# RELAYULN.net
KiCad netlist of a schematic drawn in EAGLE
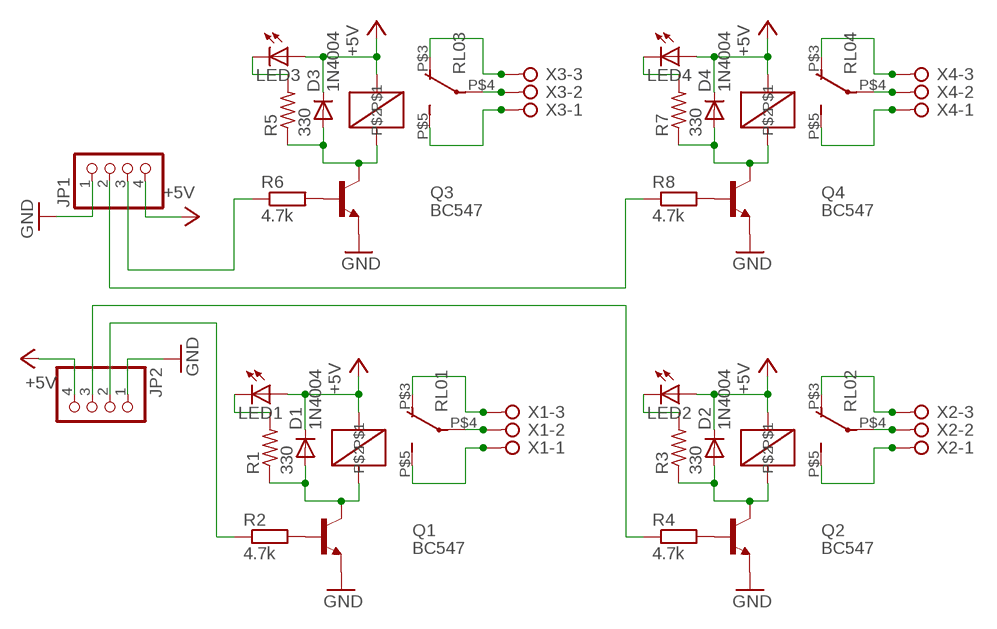
[diagram p0: schematic, sheet 1]

(export (version "E")
  (design (tool "Eeschema 10.0.6"))
  (components
    (comp (ref "D1")
      (value "1N4004")
      (footprint "eagle-import:DO41-10")
      (libsource (lib "eagle-import") (part "1N4004"))
    )
    (comp (ref "D2")
      (value "1N4004")
      (footprint "eagle-import:DO41-10")
      (libsource (lib "eagle-import") (part "1N4004"))
    )
    (comp (ref "D3")
      (value "1N4004")
      (footprint "eagle-import:DO41-10")
      (libsource (lib "eagle-import") (part "1N4004"))
    )
    (comp (ref "D4")
      (value "1N4004")
      (footprint "eagle-import:DO41-10")
      (libsource (lib "eagle-import") (part "1N4004"))
    )
    (comp (ref "JP1")
      (value "PINHD-1X4")
      (footprint "eagle-import:1X04")
      (libsource (lib "eagle-import") (part "PINHD-1X4"))
    )
    (comp (ref "JP2")
      (value "PINHD-1X4")
      (footprint "eagle-import:1X04")
      (libsource (lib "eagle-import") (part "PINHD-1X4"))
    )
    (comp (ref "LED1")
      (value "LED3MM")
      (footprint "eagle-import:LED3MM")
      (libsource (lib "eagle-import") (part "LED3MM"))
    )
    (comp (ref "LED2")
      (value "LED3MM")
      (footprint "eagle-import:LED3MM")
      (libsource (lib "eagle-import") (part "LED3MM"))
    )
    (comp (ref "LED3")
      (value "LED3MM")
      (footprint "eagle-import:LED3MM")
      (libsource (lib "eagle-import") (part "LED3MM"))
    )
    (comp (ref "LED4")
      (value "LED3MM")
      (footprint "eagle-import:LED3MM")
      (libsource (lib "eagle-import") (part "LED3MM"))
    )
    (comp (ref "Q1")
      (value "BC547")
      (footprint "eagle-import:TO92")
      (libsource (lib "eagle-import") (part "BC547"))
    )
    (comp (ref "Q2")
      (value "BC547")
      (footprint "eagle-import:TO92")
      (libsource (lib "eagle-import") (part "BC547"))
    )
    (comp (ref "Q3")
      (value "BC547")
      (footprint "eagle-import:TO92")
      (libsource (lib "eagle-import") (part "BC547"))
    )
    (comp (ref "Q4")
      (value "BC547")
      (footprint "eagle-import:TO92")
      (libsource (lib "eagle-import") (part "BC547"))
    )
    (comp (ref "R1")
      (value "330")
      (footprint "eagle-import:0207_7")
      (libsource (lib "eagle-import") (part "R-US_0207/7"))
    )
    (comp (ref "R2")
      (value "4.7k")
      (footprint "eagle-import:0207_7")
      (libsource (lib "eagle-import") (part "R-EU_0207/7"))
    )
    (comp (ref "R3")
      (value "330")
      (footprint "eagle-import:0207_7")
      (libsource (lib "eagle-import") (part "R-US_0207/7"))
    )
    (comp (ref "R4")
      (value "4.7k")
      (footprint "eagle-import:0207_7")
      (libsource (lib "eagle-import") (part "R-EU_0207/7"))
    )
    (comp (ref "R5")
      (value "330")
      (footprint "eagle-import:0207_7")
      (libsource (lib "eagle-import") (part "R-US_0207/7"))
    )
    (comp (ref "R6")
      (value "4.7k")
      (footprint "eagle-import:0207_7")
      (libsource (lib "eagle-import") (part "R-EU_0207/7"))
    )
    (comp (ref "R7")
      (value "330")
      (footprint "eagle-import:0207_7")
      (libsource (lib "eagle-import") (part "R-US_0207/7"))
    )
    (comp (ref "R8")
      (value "4.7k")
      (footprint "eagle-import:0207_7")
      (libsource (lib "eagle-import") (part "R-EU_0207/7"))
    )
    (comp (ref "RL01")
      (value "RELAY01")
      (footprint "eagle-import:RELAY01")
      (libsource (lib "eagle-import") (part "RELAY01"))
    )
    (comp (ref "RL02")
      (value "RELAY01")
      (footprint "eagle-import:RELAY01")
      (libsource (lib "eagle-import") (part "RELAY01"))
    )
    (comp (ref "RL03")
      (value "RELAY01")
      (footprint "eagle-import:RELAY01")
      (libsource (lib "eagle-import") (part "RELAY01"))
    )
    (comp (ref "RL04")
      (value "RELAY01")
      (footprint "eagle-import:RELAY01")
      (libsource (lib "eagle-import") (part "RELAY01"))
    )
    (comp (ref "X1")
      (value "W237-3E")
      (footprint "eagle-import:W237-3E")
      (libsource (lib "eagle-import") (part "W237-3E"))
    )
    (comp (ref "X2")
      (value "W237-3E")
      (footprint "eagle-import:W237-3E")
      (libsource (lib "eagle-import") (part "W237-3E"))
    )
    (comp (ref "X3")
      (value "W237-3E")
      (footprint "eagle-import:W237-3E")
      (libsource (lib "eagle-import") (part "W237-3E"))
    )
    (comp (ref "X4")
      (value "W237-3E")
      (footprint "eagle-import:W237-3E")
      (libsource (lib "eagle-import") (part "W237-3E"))
    )
  )
  (nets
    (net (code "1") (name "+5V") (class "Default")
      (node (ref "D1") (pin "C") (pinfunction "C_C") (pintype "passive"))
      (node (ref "D2") (pin "C") (pinfunction "C_C") (pintype "passive"))
      (node (ref "D3") (pin "C") (pinfunction "C_C") (pintype "passive"))
      (node (ref "D4") (pin "C") (pinfunction "C_C") (pintype "passive"))
      (node (ref "JP1") (pin "4") (pinfunction "4_4") (pintype "passive"))
      (node (ref "JP2") (pin "4") (pinfunction "4_4") (pintype "passive"))
      (node (ref "LED1") (pin "A") (pinfunction "A_A") (pintype "passive"))
      (node (ref "LED2") (pin "A") (pinfunction "A_A") (pintype "passive"))
      (node (ref "LED3") (pin "A") (pinfunction "A_A") (pintype "passive"))
      (node (ref "LED4") (pin "A") (pinfunction "A_A") (pintype "passive"))
      (node (ref "RL01") (pin "P$2") (pinfunction "P$2_P$2") (pintype "bidirectional"))
      (node (ref "RL02") (pin "P$2") (pinfunction "P$2_P$2") (pintype "bidirectional"))
      (node (ref "RL03") (pin "P$2") (pinfunction "P$2_P$2") (pintype "bidirectional"))
      (node (ref "RL04") (pin "P$2") (pinfunction "P$2_P$2") (pintype "bidirectional"))
    )
    (net (code "2") (name "GND") (class "Default")
      (node (ref "JP1") (pin "1") (pinfunction "1_1") (pintype "passive"))
      (node (ref "JP2") (pin "1") (pinfunction "1_1") (pintype "passive"))
      (node (ref "Q1") (pin "1") (pinfunction "E_1") (pintype "passive"))
      (node (ref "Q2") (pin "1") (pinfunction "E_1") (pintype "passive"))
      (node (ref "Q3") (pin "1") (pinfunction "E_1") (pintype "passive"))
      (node (ref "Q4") (pin "1") (pinfunction "E_1") (pintype "passive"))
    )
    (net (code "3") (name "Net-(JP1-Pad2)") (class "Default")
      (node (ref "JP1") (pin "2") (pinfunction "2_2") (pintype "passive"))
      (node (ref "R8") (pin "1") (pinfunction "1_1") (pintype "passive"))
    )
    (net (code "4") (name "Net-(JP1-Pad3)") (class "Default")
      (node (ref "JP1") (pin "3") (pinfunction "3_3") (pintype "passive"))
      (node (ref "R6") (pin "1") (pinfunction "1_1") (pintype "passive"))
    )
    (net (code "5") (name "Net-(JP2-Pad2)") (class "Default")
      (node (ref "JP2") (pin "2") (pinfunction "2_2") (pintype "passive"))
      (node (ref "R2") (pin "1") (pinfunction "1_1") (pintype "passive"))
    )
    (net (code "6") (name "Net-(JP2-Pad3)") (class "Default")
      (node (ref "JP2") (pin "3") (pinfunction "3_3") (pintype "passive"))
      (node (ref "R4") (pin "1") (pinfunction "1_1") (pintype "passive"))
    )
    (net (code "7") (name "Net-(LED1-C)") (class "Default")
      (node (ref "LED1") (pin "K") (pinfunction "C_K") (pintype "passive"))
      (node (ref "R1") (pin "2") (pinfunction "2_2") (pintype "passive"))
    )
    (net (code "8") (name "Net-(LED2-C)") (class "Default")
      (node (ref "LED2") (pin "K") (pinfunction "C_K") (pintype "passive"))
      (node (ref "R3") (pin "2") (pinfunction "2_2") (pintype "passive"))
    )
    (net (code "9") (name "Net-(LED3-C)") (class "Default")
      (node (ref "LED3") (pin "K") (pinfunction "C_K") (pintype "passive"))
      (node (ref "R5") (pin "2") (pinfunction "2_2") (pintype "passive"))
    )
    (net (code "10") (name "Net-(LED4-C)") (class "Default")
      (node (ref "LED4") (pin "K") (pinfunction "C_K") (pintype "passive"))
      (node (ref "R7") (pin "2") (pinfunction "2_2") (pintype "passive"))
    )
    (net (code "11") (name "Net-(Q1-B)") (class "Default")
      (node (ref "Q1") (pin "2") (pinfunction "B_2") (pintype "passive"))
      (node (ref "R2") (pin "2") (pinfunction "2_2") (pintype "passive"))
    )
    (net (code "12") (name "Net-(Q1-C)") (class "Default")
      (node (ref "D1") (pin "A") (pinfunction "A_A") (pintype "passive"))
      (node (ref "Q1") (pin "3") (pinfunction "C_3") (pintype "passive"))
      (node (ref "R1") (pin "1") (pinfunction "1_1") (pintype "passive"))
      (node (ref "RL01") (pin "P$1") (pinfunction "P$1_P$1") (pintype "bidirectional"))
    )
    (net (code "13") (name "Net-(Q2-B)") (class "Default")
      (node (ref "Q2") (pin "2") (pinfunction "B_2") (pintype "passive"))
      (node (ref "R4") (pin "2") (pinfunction "2_2") (pintype "passive"))
    )
    (net (code "14") (name "Net-(Q2-C)") (class "Default")
      (node (ref "D2") (pin "A") (pinfunction "A_A") (pintype "passive"))
      (node (ref "Q2") (pin "3") (pinfunction "C_3") (pintype "passive"))
      (node (ref "R3") (pin "1") (pinfunction "1_1") (pintype "passive"))
      (node (ref "RL02") (pin "P$1") (pinfunction "P$1_P$1") (pintype "bidirectional"))
    )
    (net (code "15") (name "Net-(Q3-B)") (class "Default")
      (node (ref "Q3") (pin "2") (pinfunction "B_2") (pintype "passive"))
      (node (ref "R6") (pin "2") (pinfunction "2_2") (pintype "passive"))
    )
    (net (code "16") (name "Net-(Q3-C)") (class "Default")
      (node (ref "D3") (pin "A") (pinfunction "A_A") (pintype "passive"))
      (node (ref "Q3") (pin "3") (pinfunction "C_3") (pintype "passive"))
      (node (ref "R5") (pin "1") (pinfunction "1_1") (pintype "passive"))
      (node (ref "RL03") (pin "P$1") (pinfunction "P$1_P$1") (pintype "bidirectional"))
    )
    (net (code "17") (name "Net-(Q4-B)") (class "Default")
      (node (ref "Q4") (pin "2") (pinfunction "B_2") (pintype "passive"))
      (node (ref "R8") (pin "2") (pinfunction "2_2") (pintype "passive"))
    )
    (net (code "18") (name "Net-(Q4-C)") (class "Default")
      (node (ref "D4") (pin "A") (pinfunction "A_A") (pintype "passive"))
      (node (ref "Q4") (pin "3") (pinfunction "C_3") (pintype "passive"))
      (node (ref "R7") (pin "1") (pinfunction "1_1") (pintype "passive"))
      (node (ref "RL04") (pin "P$1") (pinfunction "P$1_P$1") (pintype "bidirectional"))
    )
    (net (code "19") (name "Net-(RL01B-O)") (class "Default")
      (node (ref "RL01") (pin "P$3") (pinfunction "O_P$3") (pintype "passive"))
      (node (ref "X1") (pin "3") (pinfunction "KL_3") (pintype "passive"))
    )
    (net (code "20") (name "Net-(RL01B-P)") (class "Default")
      (node (ref "RL01") (pin "P$4") (pinfunction "P_P$4") (pintype "passive"))
      (node (ref "X1") (pin "2") (pinfunction "KL_2") (pintype "passive"))
    )
    (net (code "21") (name "Net-(RL01B-S)") (class "Default")
      (node (ref "RL01") (pin "P$5") (pinfunction "S_P$5") (pintype "passive"))
      (node (ref "X1") (pin "1") (pinfunction "KL_1") (pintype "passive"))
    )
    (net (code "22") (name "Net-(RL02B-O)") (class "Default")
      (node (ref "RL02") (pin "P$3") (pinfunction "O_P$3") (pintype "passive"))
      (node (ref "X2") (pin "3") (pinfunction "KL_3") (pintype "passive"))
    )
    (net (code "23") (name "Net-(RL02B-P)") (class "Default")
      (node (ref "RL02") (pin "P$4") (pinfunction "P_P$4") (pintype "passive"))
      (node (ref "X2") (pin "2") (pinfunction "KL_2") (pintype "passive"))
    )
    (net (code "24") (name "Net-(RL02B-S)") (class "Default")
      (node (ref "RL02") (pin "P$5") (pinfunction "S_P$5") (pintype "passive"))
      (node (ref "X2") (pin "1") (pinfunction "KL_1") (pintype "passive"))
    )
    (net (code "25") (name "Net-(RL03B-O)") (class "Default")
      (node (ref "RL03") (pin "P$3") (pinfunction "O_P$3") (pintype "passive"))
      (node (ref "X3") (pin "3") (pinfunction "KL_3") (pintype "passive"))
    )
    (net (code "26") (name "Net-(RL03B-P)") (class "Default")
      (node (ref "RL03") (pin "P$4") (pinfunction "P_P$4") (pintype "passive"))
      (node (ref "X3") (pin "2") (pinfunction "KL_2") (pintype "passive"))
    )
    (net (code "27") (name "Net-(RL03B-S)") (class "Default")
      (node (ref "RL03") (pin "P$5") (pinfunction "S_P$5") (pintype "passive"))
      (node (ref "X3") (pin "1") (pinfunction "KL_1") (pintype "passive"))
    )
    (net (code "28") (name "Net-(RL04B-O)") (class "Default")
      (node (ref "RL04") (pin "P$3") (pinfunction "O_P$3") (pintype "passive"))
      (node (ref "X4") (pin "3") (pinfunction "KL_3") (pintype "passive"))
    )
    (net (code "29") (name "Net-(RL04B-P)") (class "Default")
      (node (ref "RL04") (pin "P$4") (pinfunction "P_P$4") (pintype "passive"))
      (node (ref "X4") (pin "2") (pinfunction "KL_2") (pintype "passive"))
    )
    (net (code "30") (name "Net-(RL04B-S)") (class "Default")
      (node (ref "RL04") (pin "P$5") (pinfunction "S_P$5") (pintype "passive"))
      (node (ref "X4") (pin "1") (pinfunction "KL_1") (pintype "passive"))
    )
  )
)
